# GRLV_double_Rail_v0_2b_P2.net
KiCad netlist of a schematic drawn in Altium Designer
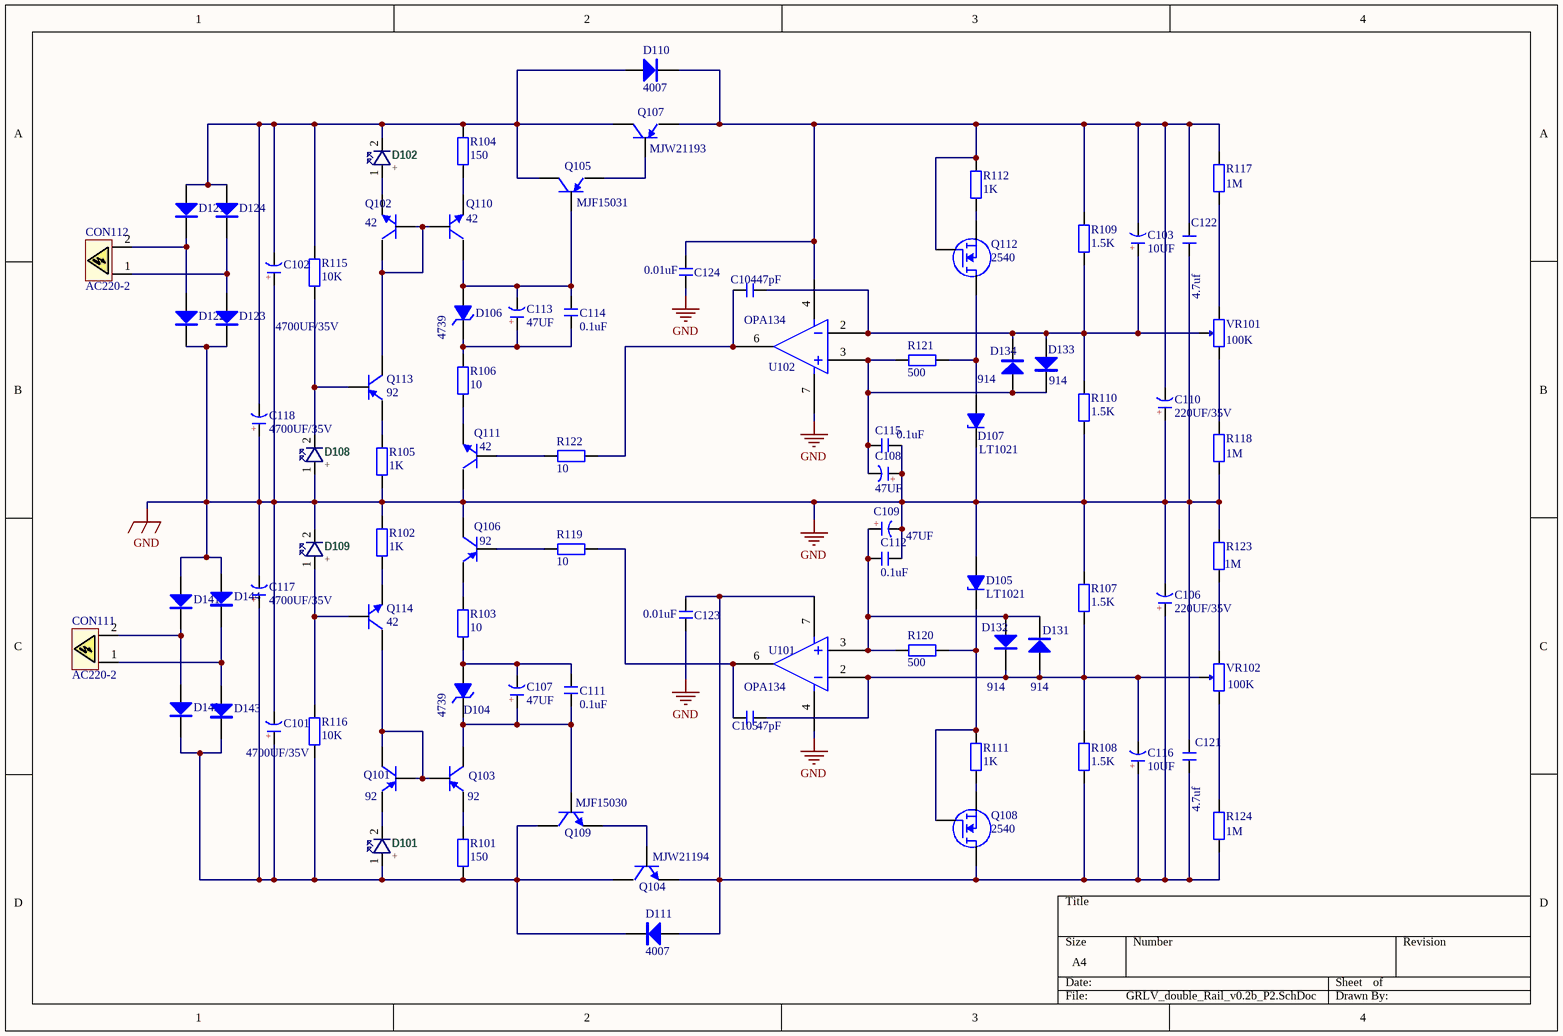
[diagram p0: GRLV_double_Rail_v0.2b_P2.SchDoc]

(export (version "E")
  (design (tool "Eeschema 10.0.6"))
  (components
    (comp (ref "C101")
      (value "4700UF/35V")
      (footprint "CAP 10*22*31.5")
      (description "直插电解电容")
      (fields (field (name "版权归属") "源创客"))
      (libsource (lib "电阻-电容-电感") (part "C-CAP"))
    )
    (comp (ref "C102")
      (value "4700UF/35V")
      (footprint "CAP 10*22*31.5")
      (description "直插电解电容")
      (fields (field (name "版权归属") "源创客"))
      (libsource (lib "电阻-电容-电感") (part "C-CAP"))
    )
    (comp (ref "C103")
      (value "10UF")
      (footprint "CAP 2.5*6.3*7")
      (description "直插电解电容")
      (fields (field (name "版权归属") "源创客"))
      (libsource (lib "电阻-电容-电感") (part "C-CAP"))
    )
    (comp (ref "C104")
      (value "47pF")
      (footprint "CBB 6.3*6.3*5")
      (description "CBB电容")
      (fields (field (name "版权归属") "源创客"))
      (libsource (lib "电阻-电容-电感") (part "C-CBB"))
    )
    (comp (ref "C105")
      (value "47pF")
      (footprint "CBB 6.3*6.3*5")
      (description "CBB电容")
      (fields (field (name "版权归属") "源创客"))
      (libsource (lib "电阻-电容-电感") (part "C-CBB"))
    )
    (comp (ref "C106")
      (value "220UF/35V")
      (footprint "CAP 3.5*8*11.5")
      (description "直插电解电容")
      (fields (field (name "版权归属") "源创客"))
      (libsource (lib "电阻-电容-电感") (part "C-CAP"))
    )
    (comp (ref "C107")
      (value "47UF")
      (footprint "CAP 2.5*6.3*11.2")
      (description "直插电解电容")
      (fields (field (name "版权归属") "源创客"))
      (libsource (lib "电阻-电容-电感") (part "C-CAP"))
    )
    (comp (ref "C108")
      (value "47UF")
      (footprint "CAP 2.5*6.3*11.2")
      (description "直插电解电容")
      (fields (field (name "版权归属") "源创客"))
      (libsource (lib "") (part "C-CAP_1"))
    )
    (comp (ref "C109")
      (value "47UF")
      (footprint "CAP 2.5*6.3*11.2")
      (description "直插电解电容")
      (fields (field (name "版权归属") "源创客"))
      (libsource (lib "") (part "C-CAP_1"))
    )
    (comp (ref "C110")
      (value "220UF/35V")
      (footprint "CAP 3.5*8*11.5")
      (description "直插电解电容")
      (fields (field (name "版权归属") "源创客"))
      (libsource (lib "电阻-电容-电感") (part "C-CAP"))
    )
    (comp (ref "C111")
      (value "0.1uF")
      (footprint "CBB 6.3*6.3*5")
      (description "CBB电容")
      (fields (field (name "版权归属") "源创客"))
      (libsource (lib "电阻-电容-电感") (part "C-CBB"))
    )
    (comp (ref "C112")
      (value "0.1uF")
      (footprint "CBB 6.3*6.3*5")
      (description "CBB电容")
      (fields (field (name "版权归属") "源创客"))
      (libsource (lib "电阻-电容-电感") (part "C-CBB"))
    )
    (comp (ref "C113")
      (value "47UF")
      (footprint "CAP 2.5*6.3*11.2")
      (description "直插电解电容")
      (fields (field (name "版权归属") "源创客"))
      (libsource (lib "电阻-电容-电感") (part "C-CAP"))
    )
    (comp (ref "C114")
      (value "0.1uF")
      (footprint "CBB 6.3*6.3*5")
      (description "CBB电容")
      (fields (field (name "版权归属") "源创客"))
      (libsource (lib "电阻-电容-电感") (part "C-CBB"))
    )
    (comp (ref "C115")
      (value "0.1uF")
      (footprint "CBB 6.3*6.3*5")
      (description "CBB电容")
      (fields (field (name "版权归属") "源创客"))
      (libsource (lib "电阻-电容-电感") (part "C-CBB"))
    )
    (comp (ref "C116")
      (value "10UF")
      (footprint "CAP 2.5*6.3*7")
      (description "直插电解电容")
      (fields (field (name "版权归属") "源创客"))
      (libsource (lib "电阻-电容-电感") (part "C-CAP"))
    )
    (comp (ref "C117")
      (value "4700UF/35V")
      (footprint "CAP 10*22*31.5")
      (description "直插电解电容")
      (fields (field (name "版权归属") "源创客"))
      (libsource (lib "电阻-电容-电感") (part "C-CAP"))
    )
    (comp (ref "C118")
      (value "4700UF/35V")
      (footprint "CAP 10*22*31.5")
      (description "直插电解电容")
      (fields (field (name "版权归属") "源创客"))
      (libsource (lib "电阻-电容-电感") (part "C-CAP"))
    )
    (comp (ref "C121")
      (value "4.7uf")
      (footprint "CBB 7.2*7.2*13")
      (description "MKS薄膜电容")
      (libsource (lib "电阻-电容-电感") (part "C-MKS"))
    )
    (comp (ref "C122")
      (value "4.7uf")
      (footprint "CBB 7.2*7.2*13")
      (description "MKS薄膜电容")
      (libsource (lib "电阻-电容-电感") (part "C-MKS"))
    )
    (comp (ref "C123")
      (value "0.01uF")
      (footprint "CBB 6.3*6.3*5")
      (description "CBB电容")
      (fields (field (name "Comment") ".01") (field (name "版权归属") "源创客"))
      (libsource (lib "电阻-电容-电感") (part "C-CBB"))
    )
    (comp (ref "C124")
      (value "0.01uF")
      (footprint "CBB 6.3*6.3*5")
      (description "CBB电容")
      (fields (field (name "Comment") ".01") (field (name "版权归属") "源创客"))
      (libsource (lib "电阻-电容-电感") (part "C-CBB"))
    )
    (comp (ref "CON111")
      (value "AC220-2")
      (footprint "HX4.0-2XS")
      (libsource (lib "Connectors") (part "AC220-2"))
    )
    (comp (ref "CON112")
      (value "AC220-2")
      (footprint "HX4.0-2XS")
      (libsource (lib "Connectors") (part "AC220-2"))
    )
    (comp (ref "D101")
      (value "+")
      (footprint "LED 3MM-R")
      (description "直插式LED")
      (libsource (lib "LED") (part "LED"))
    )
    (comp (ref "D102")
      (value "+")
      (footprint "LED 3MM-R")
      (description "直插式LED")
      (libsource (lib "LED") (part "LED"))
    )
    (comp (ref "D104")
      (value "4739")
      (footprint "DO-41")
      (description "9.1V/1W稳压管")
      (libsource (lib "二极管-整流桥") (part "1N4739"))
    )
    (comp (ref "D105")
      (value "LT1021")
      (footprint "DIP8-300_MH")
      (description "10V Precision Reference 2 Pin Config")
      (libsource (lib "电压参考") (part "LT1021-10-2P"))
    )
    (comp (ref "D106")
      (value "4739")
      (footprint "DO-41")
      (description "9.1V/1W稳压管")
      (libsource (lib "二极管-整流桥") (part "1N4739"))
    )
    (comp (ref "D107")
      (value "LT1021")
      (footprint "DIP8-300_MH")
      (description "10V Precision Reference 2 Pin Config")
      (libsource (lib "电压参考") (part "LT1021-10-2P"))
    )
    (comp (ref "D108")
      (value "+")
      (footprint "LED 3MM-R")
      (description "直插式LED")
      (libsource (lib "LED") (part "LED"))
    )
    (comp (ref "D109")
      (value "+")
      (footprint "LED 3MM-R")
      (description "直插式LED")
      (libsource (lib "LED") (part "LED"))
    )
    (comp (ref "D110")
      (value "4007")
      (footprint "DO-41")
      (description "整流二极管")
      (fields (field (name "版权归属") "源创客"))
      (libsource (lib "二极管-整流桥") (part "1N4007"))
    )
    (comp (ref "D111")
      (value "4007")
      (footprint "DO-41")
      (description "整流二极管")
      (fields (field (name "版权归属") "源创客"))
      (libsource (lib "二极管-整流桥") (part "1N4007"))
    )
    (comp (ref "D121")
      (value "VS-HFA08TB60-M3")
      (footprint "DO-15")
      (description "Ultrafast Soft Recovery Diado 8A 600V")
      (libsource (lib "二极管-整流桥") (part "VS-HFA08TB60-M3"))
    )
    (comp (ref "D122")
      (value "VS-HFA08TB60-M3")
      (footprint "DO-15")
      (description "Ultrafast Soft Recovery Diado 8A 600V")
      (libsource (lib "二极管-整流桥") (part "VS-HFA08TB60-M3"))
    )
    (comp (ref "D123")
      (value "VS-HFA08TB60-M3")
      (footprint "DO-15")
      (description "Ultrafast Soft Recovery Diado 8A 600V")
      (libsource (lib "二极管-整流桥") (part "VS-HFA08TB60-M3"))
    )
    (comp (ref "D124")
      (value "VS-HFA08TB60-M3")
      (footprint "DO-15")
      (description "Ultrafast Soft Recovery Diado 8A 600V")
      (libsource (lib "二极管-整流桥") (part "VS-HFA08TB60-M3"))
    )
    (comp (ref "D131")
      (value "914")
      (footprint "DO-35")
      (description "高速开关管 1V/0.25W")
      (libsource (lib "二极管-整流桥") (part "1N914"))
    )
    (comp (ref "D132")
      (value "914")
      (footprint "DO-35")
      (description "高速开关管 1V/0.25W")
      (libsource (lib "二极管-整流桥") (part "1N914"))
    )
    (comp (ref "D133")
      (value "914")
      (footprint "DO-35")
      (description "高速开关管 1V/0.25W")
      (libsource (lib "二极管-整流桥") (part "1N914"))
    )
    (comp (ref "D134")
      (value "914")
      (footprint "DO-35")
      (description "高速开关管 1V/0.25W")
      (libsource (lib "二极管-整流桥") (part "1N914"))
    )
    (comp (ref "D141")
      (value "VS-HFA08TB60-M3")
      (footprint "DO-15")
      (description "Ultrafast Soft Recovery Diado 8A 600V")
      (libsource (lib "二极管-整流桥") (part "VS-HFA08TB60-M3"))
    )
    (comp (ref "D142")
      (value "VS-HFA08TB60-M3")
      (footprint "DO-15")
      (description "Ultrafast Soft Recovery Diado 8A 600V")
      (libsource (lib "二极管-整流桥") (part "VS-HFA08TB60-M3"))
    )
    (comp (ref "D143")
      (value "VS-HFA08TB60-M3")
      (footprint "DO-15")
      (description "Ultrafast Soft Recovery Diado 8A 600V")
      (libsource (lib "二极管-整流桥") (part "VS-HFA08TB60-M3"))
    )
    (comp (ref "D144")
      (value "VS-HFA08TB60-M3")
      (footprint "DO-15")
      (description "Ultrafast Soft Recovery Diado 8A 600V")
      (libsource (lib "二极管-整流桥") (part "VS-HFA08TB60-M3"))
    )
    (comp (ref "Q101")
      (value "92")
      (footprint "TO92A")
      (description "High Voltage PNP Transistor")
      (libsource (lib "三极管") (part "KSP92/93"))
    )
    (comp (ref "Q102")
      (value "42")
      (footprint "TO92A")
      (description "High Voltage NPN Transistor")
      (libsource (lib "三极管") (part "KSP42/43"))
    )
    (comp (ref "Q103")
      (value "92")
      (footprint "TO92A")
      (description "High Voltage PNP Transistor")
      (libsource (lib "三极管") (part "KSP92/93"))
    )
    (comp (ref "Q104")
      (value "MJW21194")
      (footprint "TO247V")
      (description "Power NPN Transistor")
      (libsource (lib "三极管") (part "MJW21194"))
    )
    (comp (ref "Q105")
      (value "MJF15031")
      (footprint "TO220V")
      (description "Power PNP Transistor")
      (libsource (lib "三极管") (part "MJF15031"))
    )
    (comp (ref "Q106")
      (value "92")
      (footprint "TO92A")
      (description "High Voltage PNP Transistor")
      (libsource (lib "三极管") (part "KSP92/93"))
    )
    (comp (ref "Q107")
      (value "MJW21193")
      (footprint "TO247V")
      (description "Power PNP Transistor")
      (libsource (lib "三极管") (part "MJW21193"))
    )
    (comp (ref "Q108")
      (value "2540")
      (footprint "TO92A")
      (description "N沟道耗尽型DMOS场效应管 400V/150ma")
      (libsource (lib "场效应管") (part "DN2540"))
    )
    (comp (ref "Q109")
      (value "MJF15030")
      (footprint "TO220V")
      (description "Power NPN Transistor")
      (libsource (lib "三极管") (part "MJF15030"))
    )
    (comp (ref "Q110")
      (value "42")
      (footprint "TO92A")
      (description "High Voltage NPN Transistor")
      (libsource (lib "三极管") (part "KSP42/43"))
    )
    (comp (ref "Q111")
      (value "42")
      (footprint "TO92A")
      (description "High Voltage NPN Transistor")
      (libsource (lib "三极管") (part "KSP42/43"))
    )
    (comp (ref "Q112")
      (value "2540")
      (footprint "TO92A")
      (description "N沟道耗尽型DMOS场效应管 400V/150ma")
      (libsource (lib "场效应管") (part "DN2540"))
    )
    (comp (ref "Q113")
      (value "92")
      (footprint "TO92A")
      (description "High Voltage PNP Transistor")
      (libsource (lib "三极管") (part "KSP92/93"))
    )
    (comp (ref "Q114")
      (value "42")
      (footprint "TO92A")
      (description "High Voltage NPN Transistor")
      (libsource (lib "三极管") (part "KSP42/43"))
    )
    (comp (ref "R101")
      (value "150")
      (footprint "RS 1/4W")
      (description "直插色环电阻")
      (fields (field (name "版权归属") "源创客"))
      (libsource (lib "电阻-电容-电感") (part "R-CRR"))
    )
    (comp (ref "R102")
      (value "1K")
      (footprint "RS 1/4W")
      (description "直插色环电阻")
      (fields (field (name "版权归属") "源创客"))
      (libsource (lib "电阻-电容-电感") (part "R-CRR"))
    )
    (comp (ref "R103")
      (value "10")
      (footprint "RS 1/4W")
      (description "直插色环电阻")
      (fields (field (name "版权归属") "源创客"))
      (libsource (lib "电阻-电容-电感") (part "R-CRR"))
    )
    (comp (ref "R104")
      (value "150")
      (footprint "RS 1/4W")
      (description "直插色环电阻")
      (fields (field (name "版权归属") "源创客"))
      (libsource (lib "电阻-电容-电感") (part "R-CRR"))
    )
    (comp (ref "R105")
      (value "1K")
      (footprint "RS 1/4W")
      (description "直插色环电阻")
      (fields (field (name "版权归属") "源创客"))
      (libsource (lib "电阻-电容-电感") (part "R-CRR"))
    )
    (comp (ref "R106")
      (value "10")
      (footprint "RS 1/4W")
      (description "直插色环电阻")
      (fields (field (name "版权归属") "源创客"))
      (libsource (lib "电阻-电容-电感") (part "R-CRR"))
    )
    (comp (ref "R107")
      (value "1.5K")
      (footprint "RS 1/4W")
      (description "直插色环电阻")
      (fields (field (name "版权归属") "源创客"))
      (libsource (lib "电阻-电容-电感") (part "R-CRR"))
    )
    (comp (ref "R108")
      (value "1.5K")
      (footprint "RS 1/4W")
      (description "直插色环电阻")
      (fields (field (name "版权归属") "源创客"))
      (libsource (lib "电阻-电容-电感") (part "R-CRR"))
    )
    (comp (ref "R109")
      (value "1.5K")
      (footprint "RS 1/4W")
      (description "直插色环电阻")
      (fields (field (name "版权归属") "源创客"))
      (libsource (lib "电阻-电容-电感") (part "R-CRR"))
    )
    (comp (ref "R110")
      (value "1.5K")
      (footprint "RS 1/4W")
      (description "直插色环电阻")
      (fields (field (name "版权归属") "源创客"))
      (libsource (lib "电阻-电容-电感") (part "R-CRR"))
    )
    (comp (ref "R111")
      (value "1K")
      (footprint "RS 1/4W")
      (description "直插色环电阻")
      (fields (field (name "版权归属") "源创客"))
      (libsource (lib "电阻-电容-电感") (part "R-CRR"))
    )
    (comp (ref "R112")
      (value "1K")
      (footprint "RS 1/4W")
      (description "直插色环电阻")
      (fields (field (name "版权归属") "源创客"))
      (libsource (lib "电阻-电容-电感") (part "R-CRR"))
    )
    (comp (ref "R115")
      (value "10K")
      (footprint "RS 1/4W")
      (description "直插色环电阻")
      (fields (field (name "版权归属") "源创客"))
      (libsource (lib "电阻-电容-电感") (part "R-CRR"))
    )
    (comp (ref "R116")
      (value "10K")
      (footprint "RS 1/4W")
      (description "直插色环电阻")
      (fields (field (name "版权归属") "源创客"))
      (libsource (lib "电阻-电容-电感") (part "R-CRR"))
    )
    (comp (ref "R117")
      (value "1M")
      (footprint "RS 1/4W")
      (description "直插色环电阻")
      (fields (field (name "版权归属") "源创客"))
      (libsource (lib "电阻-电容-电感") (part "R-CRR"))
    )
    (comp (ref "R118")
      (value "1M")
      (footprint "RS 1/4W")
      (description "直插色环电阻")
      (fields (field (name "版权归属") "源创客"))
      (libsource (lib "电阻-电容-电感") (part "R-CRR"))
    )
    (comp (ref "R119")
      (value "10")
      (footprint "RS 1/4W")
      (description "直插色环电阻")
      (fields (field (name "版权归属") "源创客"))
      (libsource (lib "电阻-电容-电感") (part "R-CRR"))
    )
    (comp (ref "R120")
      (value "500")
      (footprint "RS 1/4W")
      (description "直插色环电阻")
      (fields (field (name "版权归属") "源创客"))
      (libsource (lib "电阻-电容-电感") (part "R-CRR"))
    )
    (comp (ref "R121")
      (value "500")
      (footprint "RS 1/4W")
      (description "直插色环电阻")
      (fields (field (name "版权归属") "源创客"))
      (libsource (lib "电阻-电容-电感") (part "R-CRR"))
    )
    (comp (ref "R122")
      (value "10")
      (footprint "RS 1/4W")
      (description "直插色环电阻")
      (fields (field (name "版权归属") "源创客"))
      (libsource (lib "电阻-电容-电感") (part "R-CRR"))
    )
    (comp (ref "R123")
      (value "1M")
      (footprint "RS 1/4W")
      (description "直插色环电阻")
      (fields (field (name "版权归属") "源创客"))
      (libsource (lib "电阻-电容-电感") (part "R-CRR"))
    )
    (comp (ref "R124")
      (value "1M")
      (footprint "RS 1/4W")
      (description "直插色环电阻")
      (fields (field (name "版权归属") "源创客"))
      (libsource (lib "电阻-电容-电感") (part "R-CRR"))
    )
    (comp (ref "U101") (value "OPA134") (footprint "DIP8-300_MH") (libsource (lib "运放") (part "OPA134PA")))
    (comp (ref "U102") (value "OPA134") (footprint "DIP8-300_MH") (libsource (lib "运放") (part "OPA134PA")))
    (comp (ref "VR101")
      (value "100K")
      (footprint "RS 1/2W-VR")
      (description "直插可调电阻-顶调")
      (libsource (lib "电阻-电容-电感") (part "VR-W"))
    )
    (comp (ref "VR102")
      (value "100K")
      (footprint "RS 1/2W-VR")
      (description "直插可调电阻-顶调")
      (libsource (lib "电阻-电容-电感") (part "VR-W"))
    )
  )
  (nets
    (net (code "1") (name "GND") (class "Default")
      (node (ref "C101") (pin "2") (pinfunction "K_2") (pintype "passive"))
      (node (ref "C102") (pin "1") (pinfunction "A_1") (pintype "passive"))
      (node (ref "C106") (pin "2") (pinfunction "K_2") (pintype "passive"))
      (node (ref "C108") (pin "1") (pinfunction "A_1") (pintype "passive"))
      (node (ref "C109") (pin "2") (pinfunction "K_2") (pintype "passive"))
      (node (ref "C110") (pin "1") (pinfunction "A_1") (pintype "passive"))
      (node (ref "C112") (pin "2") (pinfunction "2_2") (pintype "passive"))
      (node (ref "C115") (pin "2") (pinfunction "2_2") (pintype "passive"))
      (node (ref "C117") (pin "2") (pinfunction "K_2") (pintype "passive"))
      (node (ref "C118") (pin "1") (pinfunction "A_1") (pintype "passive"))
      (node (ref "C121") (pin "2") (pinfunction "2_2") (pintype "passive"))
      (node (ref "C122") (pin "1") (pinfunction "1_1") (pintype "passive"))
      (node (ref "C123") (pin "1") (pinfunction "1_1") (pintype "passive"))
      (node (ref "C124") (pin "1") (pinfunction "1_1") (pintype "passive"))
      (node (ref "D105") (pin "4") (pinfunction "A_4") (pintype "passive"))
      (node (ref "D107") (pin "6") (pinfunction "K_6") (pintype "passive"))
      (node (ref "D108") (pin "1") (pinfunction "A_1") (pintype "passive"))
      (node (ref "D109") (pin "2") (pinfunction "K_2") (pintype "passive"))
      (node (ref "D122") (pin "1") (pinfunction "Cathode_1") (pintype "passive"))
      (node (ref "D123") (pin "1") (pinfunction "Cathode_1") (pintype "passive"))
      (node (ref "D141") (pin "2") (pinfunction "Anode_2") (pintype "passive"))
      (node (ref "D144") (pin "2") (pinfunction "Anode_2") (pintype "passive"))
      (node (ref "Q106") (pin "3") (pinfunction "C_3") (pintype "passive"))
      (node (ref "Q111") (pin "3") (pinfunction "C_3") (pintype "passive"))
      (node (ref "R102") (pin "2") (pinfunction "2_2") (pintype "passive"))
      (node (ref "R105") (pin "1") (pinfunction "1_1") (pintype "passive"))
      (node (ref "R107") (pin "2") (pinfunction "2_2") (pintype "passive"))
      (node (ref "R110") (pin "1") (pinfunction "1_1") (pintype "passive"))
      (node (ref "R118") (pin "1") (pinfunction "1_1") (pintype "passive"))
      (node (ref "R123") (pin "2") (pinfunction "2_2") (pintype "passive"))
      (node (ref "U101") (pin "4") (pinfunction "V-_4") (pintype "passive"))
      (node (ref "U102") (pin "7") (pinfunction "V+_7") (pintype "passive"))
    )
    (net (code "2") (name "Net-(C101-A)") (class "Default")
      (node (ref "C101") (pin "1") (pinfunction "A_1") (pintype "passive"))
      (node (ref "C117") (pin "1") (pinfunction "A_1") (pintype "passive"))
      (node (ref "D101") (pin "1") (pinfunction "A_1") (pintype "passive"))
      (node (ref "D111") (pin "2") (pinfunction "K_2") (pintype "passive"))
      (node (ref "D142") (pin "1") (pinfunction "Cathode_1") (pintype "passive"))
      (node (ref "D143") (pin "1") (pinfunction "Cathode_1") (pintype "passive"))
      (node (ref "Q104") (pin "2") (pinfunction "C_2") (pintype "passive"))
      (node (ref "Q109") (pin "2") (pinfunction "C_2") (pintype "passive"))
      (node (ref "R101") (pin "1") (pinfunction "1_1") (pintype "passive"))
      (node (ref "R116") (pin "1") (pinfunction "1_1") (pintype "passive"))
    )
    (net (code "3") (name "Net-(C102-K)") (class "Default")
      (node (ref "C102") (pin "2") (pinfunction "K_2") (pintype "passive"))
      (node (ref "C118") (pin "2") (pinfunction "K_2") (pintype "passive"))
      (node (ref "D102") (pin "2") (pinfunction "K_2") (pintype "passive"))
      (node (ref "D110") (pin "1") (pinfunction "A_1") (pintype "passive"))
      (node (ref "D121") (pin "2") (pinfunction "Anode_2") (pintype "passive"))
      (node (ref "D124") (pin "2") (pinfunction "Anode_2") (pintype "passive"))
      (node (ref "Q105") (pin "2") (pinfunction "C_2") (pintype "passive"))
      (node (ref "Q107") (pin "2") (pinfunction "C_2") (pintype "passive"))
      (node (ref "R104") (pin "2") (pinfunction "2_2") (pintype "passive"))
      (node (ref "R115") (pin "2") (pinfunction "2_2") (pintype "passive"))
    )
    (net (code "4") (name "Net-(C103-A)") (class "Default")
      (node (ref "C103") (pin "1") (pinfunction "A_1") (pintype "passive"))
      (node (ref "C104") (pin "2") (pinfunction "2_2") (pintype "passive"))
      (node (ref "D133") (pin "1") (pinfunction "A_1") (pintype "passive"))
      (node (ref "D134") (pin "2") (pinfunction "K_2") (pintype "passive"))
      (node (ref "R109") (pin "1") (pinfunction "1_1") (pintype "passive"))
      (node (ref "R110") (pin "2") (pinfunction "2_2") (pintype "passive"))
      (node (ref "U102") (pin "2") (pinfunction "-in_2") (pintype "passive"))
      (node (ref "VR101") (pin "3") (pinfunction "3_3") (pintype "passive"))
    )
    (net (code "5") (name "Net-(C103-K)") (class "Default")
      (node (ref "C103") (pin "2") (pinfunction "K_2") (pintype "passive"))
      (node (ref "C110") (pin "2") (pinfunction "K_2") (pintype "passive"))
      (node (ref "C122") (pin "2") (pinfunction "2_2") (pintype "passive"))
      (node (ref "C124") (pin "2") (pinfunction "2_2") (pintype "passive"))
      (node (ref "D110") (pin "2") (pinfunction "K_2") (pintype "passive"))
      (node (ref "Q107") (pin "3") (pinfunction "E_3") (pintype "passive"))
      (node (ref "Q112") (pin "2") (pinfunction "G_2") (pintype "passive"))
      (node (ref "R109") (pin "2") (pinfunction "2_2") (pintype "passive"))
      (node (ref "R112") (pin "2") (pinfunction "2_2") (pintype "passive"))
      (node (ref "R117") (pin "2") (pinfunction "2_2") (pintype "passive"))
      (node (ref "U102") (pin "4") (pinfunction "V-_4") (pintype "passive"))
    )
    (net (code "6") (name "Net-(C106-A)") (class "Default")
      (node (ref "C106") (pin "1") (pinfunction "A_1") (pintype "passive"))
      (node (ref "C116") (pin "1") (pinfunction "A_1") (pintype "passive"))
      (node (ref "C121") (pin "1") (pinfunction "1_1") (pintype "passive"))
      (node (ref "C123") (pin "2") (pinfunction "2_2") (pintype "passive"))
      (node (ref "D111") (pin "1") (pinfunction "A_1") (pintype "passive"))
      (node (ref "Q104") (pin "3") (pinfunction "E_3") (pintype "passive"))
      (node (ref "Q108") (pin "3") (pinfunction "D_3") (pintype "passive"))
      (node (ref "R108") (pin "1") (pinfunction "1_1") (pintype "passive"))
      (node (ref "R124") (pin "1") (pinfunction "1_1") (pintype "passive"))
      (node (ref "U101") (pin "7") (pinfunction "V+_7") (pintype "passive"))
    )
    (net (code "7") (name "Net-(C107-A)") (class "Default")
      (node (ref "C107") (pin "1") (pinfunction "A_1") (pintype "passive"))
      (node (ref "C111") (pin "1") (pinfunction "1_1") (pintype "passive"))
      (node (ref "D104") (pin "2") (pinfunction "K_2") (pintype "passive"))
      (node (ref "Q103") (pin "3") (pinfunction "C_3") (pintype "passive"))
      (node (ref "Q109") (pin "1") (pinfunction "B_1") (pintype "passive"))
    )
    (net (code "8") (name "Net-(C107-K)") (class "Default")
      (node (ref "C107") (pin "2") (pinfunction "K_2") (pintype "passive"))
      (node (ref "C111") (pin "2") (pinfunction "2_2") (pintype "passive"))
      (node (ref "D104") (pin "1") (pinfunction "A_1") (pintype "passive"))
      (node (ref "R103") (pin "1") (pinfunction "1_1") (pintype "passive"))
    )
    (net (code "9") (name "Net-(C108-K)") (class "Default")
      (node (ref "C108") (pin "2") (pinfunction "K_2") (pintype "passive"))
      (node (ref "C115") (pin "1") (pinfunction "1_1") (pintype "passive"))
      (node (ref "D133") (pin "2") (pinfunction "K_2") (pintype "passive"))
      (node (ref "D134") (pin "1") (pinfunction "A_1") (pintype "passive"))
      (node (ref "R121") (pin "1") (pinfunction "1_1") (pintype "passive"))
      (node (ref "U102") (pin "3") (pinfunction "+in_3") (pintype "passive"))
    )
    (net (code "10") (name "Net-(C109-A)") (class "Default")
      (node (ref "C109") (pin "1") (pinfunction "A_1") (pintype "passive"))
      (node (ref "C112") (pin "1") (pinfunction "1_1") (pintype "passive"))
      (node (ref "D131") (pin "2") (pinfunction "K_2") (pintype "passive"))
      (node (ref "D132") (pin "1") (pinfunction "A_1") (pintype "passive"))
      (node (ref "R120") (pin "1") (pinfunction "1_1") (pintype "passive"))
      (node (ref "U101") (pin "3") (pinfunction "+in_3") (pintype "passive"))
    )
    (net (code "11") (name "Net-(C113-A)") (class "Default")
      (node (ref "C113") (pin "1") (pinfunction "A_1") (pintype "passive"))
      (node (ref "C114") (pin "1") (pinfunction "1_1") (pintype "passive"))
      (node (ref "D106") (pin "2") (pinfunction "K_2") (pintype "passive"))
      (node (ref "R106") (pin "2") (pinfunction "2_2") (pintype "passive"))
    )
    (net (code "12") (name "Net-(C113-K)") (class "Default")
      (node (ref "C113") (pin "2") (pinfunction "K_2") (pintype "passive"))
      (node (ref "C114") (pin "2") (pinfunction "2_2") (pintype "passive"))
      (node (ref "D106") (pin "1") (pinfunction "A_1") (pintype "passive"))
      (node (ref "Q105") (pin "1") (pinfunction "B_1") (pintype "passive"))
      (node (ref "Q110") (pin "3") (pinfunction "C_3") (pintype "passive"))
    )
    (net (code "13") (name "Net-(C116-K)") (class "Default")
      (node (ref "C105") (pin "2") (pinfunction "2_2") (pintype "passive"))
      (node (ref "C116") (pin "2") (pinfunction "K_2") (pintype "passive"))
      (node (ref "D131") (pin "1") (pinfunction "A_1") (pintype "passive"))
      (node (ref "D132") (pin "2") (pinfunction "K_2") (pintype "passive"))
      (node (ref "R107") (pin "1") (pinfunction "1_1") (pintype "passive"))
      (node (ref "R108") (pin "2") (pinfunction "2_2") (pintype "passive"))
      (node (ref "U101") (pin "2") (pinfunction "-in_2") (pintype "passive"))
      (node (ref "VR102") (pin "3") (pinfunction "3_3") (pintype "passive"))
    )
    (net (code "14") (name "Net-(CON111-G)") (class "Default")
      (node (ref "CON111") (pin "2") (pinfunction "G_2") (pintype "passive"))
      (node (ref "D141") (pin "1") (pinfunction "Cathode_1") (pintype "passive"))
      (node (ref "D142") (pin "2") (pinfunction "Anode_2") (pintype "passive"))
    )
    (net (code "15") (name "Net-(CON111-L)") (class "Default")
      (node (ref "CON111") (pin "1") (pinfunction "L_1") (pintype "passive"))
      (node (ref "D143") (pin "2") (pinfunction "Anode_2") (pintype "passive"))
      (node (ref "D144") (pin "1") (pinfunction "Cathode_1") (pintype "passive"))
    )
    (net (code "16") (name "Net-(CON112-G)") (class "Default")
      (node (ref "CON112") (pin "2") (pinfunction "G_2") (pintype "passive"))
      (node (ref "D121") (pin "1") (pinfunction "Cathode_1") (pintype "passive"))
      (node (ref "D122") (pin "2") (pinfunction "Anode_2") (pintype "passive"))
    )
    (net (code "17") (name "Net-(CON112-L)") (class "Default")
      (node (ref "CON112") (pin "1") (pinfunction "L_1") (pintype "passive"))
      (node (ref "D123") (pin "2") (pinfunction "Anode_2") (pintype "passive"))
      (node (ref "D124") (pin "1") (pinfunction "Cathode_1") (pintype "passive"))
    )
    (net (code "18") (name "Net-(D101-K)") (class "Default")
      (node (ref "D101") (pin "2") (pinfunction "K_2") (pintype "passive"))
      (node (ref "Q101") (pin "1") (pinfunction "E_1") (pintype "passive"))
    )
    (net (code "19") (name "Net-(D102-A)") (class "Default")
      (node (ref "D102") (pin "1") (pinfunction "A_1") (pintype "passive"))
      (node (ref "Q102") (pin "1") (pinfunction "E_1") (pintype "passive"))
    )
    (net (code "20") (name "Net-(D105-K)") (class "Default")
      (node (ref "D105") (pin "6") (pinfunction "K_6") (pintype "passive"))
      (node (ref "Q108") (pin "2") (pinfunction "G_2") (pintype "passive"))
      (node (ref "R111") (pin "2") (pinfunction "2_2") (pintype "passive"))
      (node (ref "R120") (pin "2") (pinfunction "2_2") (pintype "passive"))
    )
    (net (code "21") (name "Net-(D107-A)") (class "Default")
      (node (ref "D107") (pin "4") (pinfunction "A_4") (pintype "passive"))
      (node (ref "Q112") (pin "3") (pinfunction "D_3") (pintype "passive"))
      (node (ref "R121") (pin "2") (pinfunction "2_2") (pintype "passive"))
    )
    (net (code "22") (name "Net-(D108-K)") (class "Default")
      (node (ref "D108") (pin "2") (pinfunction "K_2") (pintype "passive"))
      (node (ref "Q113") (pin "2") (pinfunction "B_2") (pintype "passive"))
      (node (ref "R115") (pin "1") (pinfunction "1_1") (pintype "passive"))
    )
    (net (code "23") (name "Net-(D109-A)") (class "Default")
      (node (ref "D109") (pin "1") (pinfunction "A_1") (pintype "passive"))
      (node (ref "Q114") (pin "2") (pinfunction "B_2") (pintype "passive"))
      (node (ref "R116") (pin "2") (pinfunction "2_2") (pintype "passive"))
    )
    (net (code "24") (name "Net-(Q101-B)") (class "Default")
      (node (ref "Q101") (pin "2") (pinfunction "B_2") (pintype "passive"))
      (node (ref "Q101") (pin "3") (pinfunction "C_3") (pintype "passive"))
      (node (ref "Q103") (pin "2") (pinfunction "B_2") (pintype "passive"))
      (node (ref "Q114") (pin "3") (pinfunction "C_3") (pintype "passive"))
    )
    (net (code "25") (name "Net-(Q102-B)") (class "Default")
      (node (ref "Q102") (pin "2") (pinfunction "B_2") (pintype "passive"))
      (node (ref "Q102") (pin "3") (pinfunction "C_3") (pintype "passive"))
      (node (ref "Q110") (pin "2") (pinfunction "B_2") (pintype "passive"))
      (node (ref "Q113") (pin "3") (pinfunction "C_3") (pintype "passive"))
    )
    (net (code "26") (name "Net-(Q103-E)") (class "Default")
      (node (ref "Q103") (pin "1") (pinfunction "E_1") (pintype "passive"))
      (node (ref "R101") (pin "2") (pinfunction "2_2") (pintype "passive"))
    )
    (net (code "27") (name "Net-(Q104-B)") (class "Default")
      (node (ref "Q104") (pin "1") (pinfunction "B_1") (pintype "passive"))
      (node (ref "Q109") (pin "3") (pinfunction "E_3") (pintype "passive"))
    )
    (net (code "28") (name "Net-(Q105-E)") (class "Default")
      (node (ref "Q105") (pin "3") (pinfunction "E_3") (pintype "passive"))
      (node (ref "Q107") (pin "1") (pinfunction "B_1") (pintype "passive"))
    )
    (net (code "29") (name "Net-(Q106-B)") (class "Default")
      (node (ref "Q106") (pin "2") (pinfunction "B_2") (pintype "passive"))
      (node (ref "R119") (pin "1") (pinfunction "1_1") (pintype "passive"))
    )
    (net (code "30") (name "Net-(Q106-E)") (class "Default")
      (node (ref "Q106") (pin "1") (pinfunction "E_1") (pintype "passive"))
      (node (ref "R103") (pin "2") (pinfunction "2_2") (pintype "passive"))
    )
    (net (code "31") (name "Net-(Q108-S)") (class "Default")
      (node (ref "Q108") (pin "1") (pinfunction "S_1") (pintype "passive"))
      (node (ref "R111") (pin "1") (pinfunction "1_1") (pintype "passive"))
    )
    (net (code "32") (name "Net-(Q110-E)") (class "Default")
      (node (ref "Q110") (pin "1") (pinfunction "E_1") (pintype "passive"))
      (node (ref "R104") (pin "1") (pinfunction "1_1") (pintype "passive"))
    )
    (net (code "33") (name "Net-(Q111-B)") (class "Default")
      (node (ref "Q111") (pin "2") (pinfunction "B_2") (pintype "passive"))
      (node (ref "R122") (pin "1") (pinfunction "1_1") (pintype "passive"))
    )
    (net (code "34") (name "Net-(Q111-E)") (class "Default")
      (node (ref "Q111") (pin "1") (pinfunction "E_1") (pintype "passive"))
      (node (ref "R106") (pin "1") (pinfunction "1_1") (pintype "passive"))
    )
    (net (code "35") (name "Net-(Q112-S)") (class "Default")
      (node (ref "Q112") (pin "1") (pinfunction "S_1") (pintype "passive"))
      (node (ref "R112") (pin "1") (pinfunction "1_1") (pintype "passive"))
    )
    (net (code "36") (name "Net-(Q113-E)") (class "Default")
      (node (ref "Q113") (pin "1") (pinfunction "E_1") (pintype "passive"))
      (node (ref "R105") (pin "2") (pinfunction "2_2") (pintype "passive"))
    )
    (net (code "37") (name "Net-(Q114-E)") (class "Default")
      (node (ref "Q114") (pin "1") (pinfunction "E_1") (pintype "passive"))
      (node (ref "R102") (pin "1") (pinfunction "1_1") (pintype "passive"))
    )
    (net (code "38") (name "Net-(R117-Pad1)") (class "Default")
      (node (ref "R117") (pin "1") (pinfunction "1_1") (pintype "passive"))
      (node (ref "VR101") (pin "2") (pinfunction "2_2") (pintype "passive"))
    )
    (net (code "39") (name "Net-(R118-Pad2)") (class "Default")
      (node (ref "R118") (pin "2") (pinfunction "2_2") (pintype "passive"))
      (node (ref "VR101") (pin "1") (pinfunction "1_1") (pintype "passive"))
    )
    (net (code "40") (name "Net-(R123-Pad1)") (class "Default")
      (node (ref "R123") (pin "1") (pinfunction "1_1") (pintype "passive"))
      (node (ref "VR102") (pin "2") (pinfunction "2_2") (pintype "passive"))
    )
    (net (code "41") (name "Net-(R124-Pad2)") (class "Default")
      (node (ref "R124") (pin "2") (pinfunction "2_2") (pintype "passive"))
      (node (ref "VR102") (pin "1") (pinfunction "1_1") (pintype "passive"))
    )
    (net (code "42") (name "Net-(U101-out)") (class "Default")
      (node (ref "C105") (pin "1") (pinfunction "1_1") (pintype "passive"))
      (node (ref "R119") (pin "2") (pinfunction "2_2") (pintype "passive"))
      (node (ref "U101") (pin "6") (pinfunction "out_6") (pintype "passive"))
    )
    (net (code "43") (name "Net-(U102-out)") (class "Default")
      (node (ref "C104") (pin "1") (pinfunction "1_1") (pintype "passive"))
      (node (ref "R122") (pin "2") (pinfunction "2_2") (pintype "passive"))
      (node (ref "U102") (pin "6") (pinfunction "out_6") (pintype "passive"))
    )
  )
)
